# power.net
KiCad netlist of a schematic drawn in Altium Designer
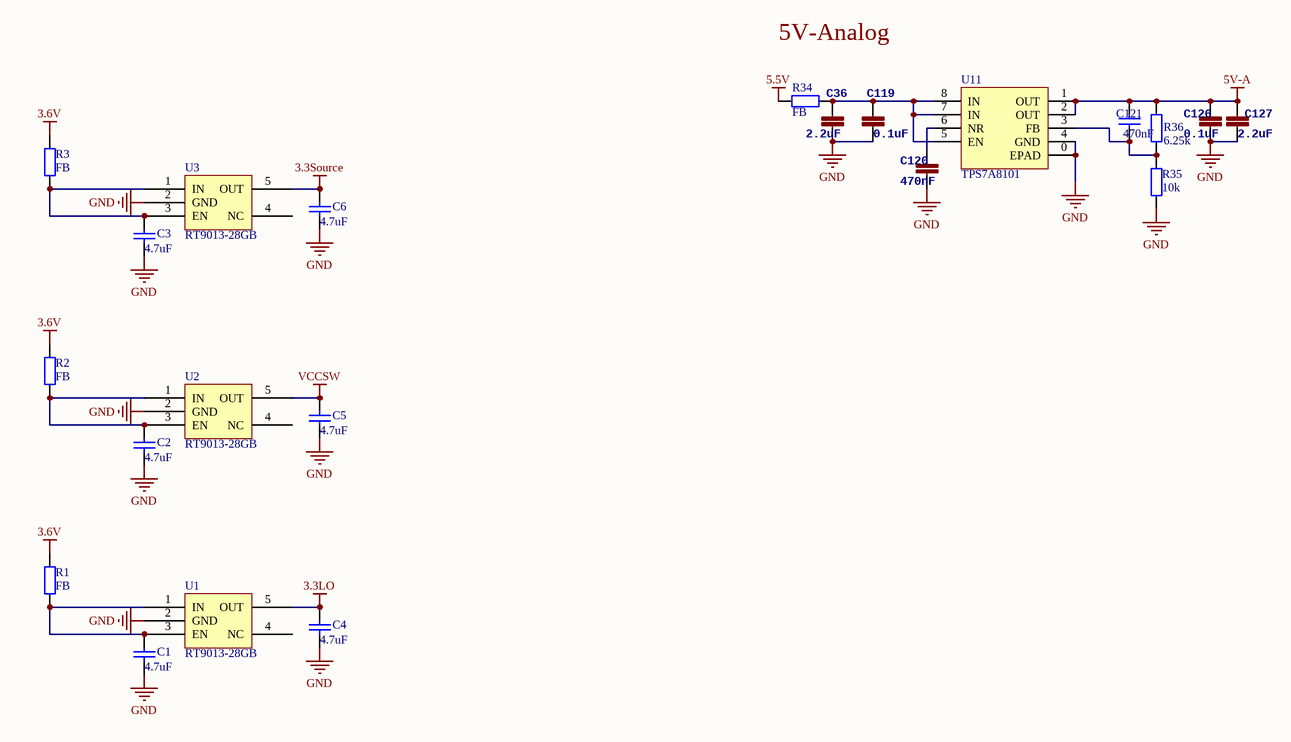
[diagram p0: power.SchDoc]

(export (version "E")
  (design (tool "Eeschema 10.0.6"))
  (components
    (comp (ref "C1")
      (value "4.7uF")
      (footprint "0603L")
      (description "Capacitor")
      (fields (field (name "PUBLISHER") "Altium Limited"))
      (libsource (lib "RTC6705") (part "Cap"))
    )
    (comp (ref "C2")
      (value "4.7uF")
      (footprint "0603L")
      (description "Capacitor")
      (fields (field (name "PUBLISHER") "Altium Limited"))
      (libsource (lib "RTC6705") (part "Cap"))
    )
    (comp (ref "C3")
      (value "4.7uF")
      (footprint "0603L")
      (description "Capacitor")
      (fields (field (name "PUBLISHER") "Altium Limited"))
      (libsource (lib "RTC6705") (part "Cap"))
    )
    (comp (ref "C4")
      (value "4.7uF")
      (footprint "0603L")
      (description "Capacitor")
      (fields (field (name "PUBLISHER") "Altium Limited"))
      (libsource (lib "RTC6705") (part "Cap"))
    )
    (comp (ref "C5")
      (value "4.7uF")
      (footprint "0603L")
      (description "Capacitor")
      (fields (field (name "PUBLISHER") "Altium Limited"))
      (libsource (lib "RTC6705") (part "Cap"))
    )
    (comp (ref "C6")
      (value "4.7uF")
      (footprint "0603L")
      (description "Capacitor")
      (fields (field (name "PUBLISHER") "Altium Limited"))
      (libsource (lib "RTC6705") (part "Cap"))
    )
    (comp (ref "C36")
      (value "2.2uF")
      (footprint "0603L")
      (description "<b>Capacitor</b>\nStandard 0603 ceramic capacitor, and 0.1\" leaded capacitor.")
      (fields (field (name "PARTNO") "CC0402ZRY5V7BB104"))
      (libsource (lib "pixhawk2") (part "CAP0402-CAP"))
    )
    (comp (ref "C119")
      (value "0.1uF")
      (footprint "0402")
      (description "<b>Capacitor</b>\nStandard 0603 ceramic capacitor, and 0.1\" leaded capacitor.")
      (fields (field (name "PARTNO") "CC0402ZRY5V7BB104"))
      (libsource (lib "*") (part "CAP0402-CAP"))
    )
    (comp (ref "C120")
      (value "470nF")
      (footprint "0402")
      (description "<b>Capacitor</b>\nStandard 0603 ceramic capacitor, and 0.1\" leaded capacitor.")
      (fields (field (name "PARTNO") "CC0402ZRY5V7BB104"))
      (libsource (lib "*") (part "CAP0402-CAP"))
    )
    (comp (ref "C121")
      (value "470nF")
      (footprint "0402")
      (description "Capacitor")
      (fields (field (name "PUBLISHER") "Altium Limited"))
      (libsource (lib "RTC6705") (part "Cap"))
    )
    (comp (ref "C126")
      (value "0.1uF")
      (footprint "0603L")
      (description "<b>Capacitor</b>\nStandard 0603 ceramic capacitor, and 0.1\" leaded capacitor.")
      (fields (field (name "PARTNO") "CC0402ZRY5V7BB104"))
      (libsource (lib "*") (part "CAP0402-CAP"))
    )
    (comp (ref "C127")
      (value "2.2uF")
      (footprint "0603L")
      (description "<b>Capacitor</b>\nStandard 0603 ceramic capacitor, and 0.1\" leaded capacitor.")
      (fields (field (name "PARTNO") "CC0402ZRY5V7BB104"))
      (libsource (lib "pixhawk2") (part "CAP0402-CAP"))
    )
    (comp (ref "R1")
      (value "FB")
      (footprint "0603L")
      (description "Resistor")
      (fields (field (name "PUBLISHER") "Altium Limited"))
      (libsource (lib "Miscellaneous Devices") (part "Res2"))
    )
    (comp (ref "R2")
      (value "FB")
      (footprint "0603L")
      (description "Resistor")
      (fields (field (name "PUBLISHER") "Altium Limited"))
      (libsource (lib "Miscellaneous Devices") (part "Res2"))
    )
    (comp (ref "R3")
      (value "FB")
      (footprint "0603L")
      (description "Resistor")
      (fields (field (name "PUBLISHER") "Altium Limited"))
      (libsource (lib "Miscellaneous Devices") (part "Res2"))
    )
    (comp (ref "R34")
      (value "FB")
      (footprint "0603L")
      (description "Resistor")
      (fields (field (name "PUBLISHER") "Altium Limited"))
      (libsource (lib "") (part "Res2_1"))
    )
    (comp (ref "R35")
      (value "10k")
      (footprint "0402")
      (description "Resistor")
      (fields (field (name "PUBLISHER") "Altium Limited"))
      (libsource (lib "") (part "Res2_2"))
    )
    (comp (ref "R36")
      (value "6.25k")
      (footprint "0402")
      (description "Resistor")
      (fields (field (name "PUBLISHER") "Altium Limited"))
      (libsource (lib "") (part "Res2_2"))
    )
    (comp (ref "U1") (value "RT9013-28GB") (footprint "SOT23-5") (libsource (lib "RTC6705") (part "LP5907")))
    (comp (ref "U2") (value "RT9013-28GB") (footprint "SOT23-5") (libsource (lib "RTC6705") (part "LP5907")))
    (comp (ref "U3") (value "RT9013-28GB") (footprint "SOT23-5") (libsource (lib "RTC6705") (part "LP5907")))
    (comp (ref "U11")
      (value "TPS7A8101")
      (footprint "TPS7A8101")
      (libsource (lib "F4SDR") (part "TPS7A8101"))
    )
  )
  (nets
    (net (code "1") (name "3.3LO") (class "Default")
      (node (ref "C4") (pin "2") (pinfunction "2_2") (pintype "passive"))
      (node (ref "U1") (pin "5") (pinfunction "OUT_5") (pintype "passive"))
    )
    (net (code "2") (name "3.3Source") (class "Default")
      (node (ref "C6") (pin "2") (pinfunction "2_2") (pintype "passive"))
      (node (ref "U3") (pin "5") (pinfunction "OUT_5") (pintype "passive"))
    )
    (net (code "3") (name "3.6V") (class "Default")
      (node (ref "R1") (pin "2") (pinfunction "2_2") (pintype "passive"))
      (node (ref "R2") (pin "2") (pinfunction "2_2") (pintype "passive"))
      (node (ref "R3") (pin "2") (pinfunction "2_2") (pintype "passive"))
    )
    (net (code "4") (name "5.5V") (class "Default")
      (node (ref "R34") (pin "2") (pinfunction "2_2") (pintype "passive"))
    )
    (net (code "5") (name "5V-A") (class "Default")
      (node (ref "C121") (pin "1") (pinfunction "1_1") (pintype "passive"))
      (node (ref "C126") (pin "2") (pinfunction "2_2") (pintype "passive"))
      (node (ref "C127") (pin "2") (pinfunction "2_2") (pintype "passive"))
      (node (ref "R36") (pin "1") (pinfunction "1_1") (pintype "passive"))
      (node (ref "U11") (pin "1") (pinfunction "OUT_1") (pintype "passive"))
      (node (ref "U11") (pin "2") (pinfunction "OUT_2") (pintype "passive"))
    )
    (net (code "6") (name "GND") (class "Default")
      (node (ref "C1") (pin "1") (pinfunction "1_1") (pintype "passive"))
      (node (ref "C119") (pin "1") (pinfunction "1_1") (pintype "passive"))
      (node (ref "C120") (pin "1") (pinfunction "1_1") (pintype "passive"))
      (node (ref "C126") (pin "1") (pinfunction "1_1") (pintype "passive"))
      (node (ref "C127") (pin "1") (pinfunction "1_1") (pintype "passive"))
      (node (ref "C2") (pin "1") (pinfunction "1_1") (pintype "passive"))
      (node (ref "C3") (pin "1") (pinfunction "1_1") (pintype "passive"))
      (node (ref "C36") (pin "1") (pinfunction "1_1") (pintype "passive"))
      (node (ref "C4") (pin "1") (pinfunction "1_1") (pintype "passive"))
      (node (ref "C5") (pin "1") (pinfunction "1_1") (pintype "passive"))
      (node (ref "C6") (pin "1") (pinfunction "1_1") (pintype "passive"))
      (node (ref "R35") (pin "2") (pinfunction "2_2") (pintype "passive"))
      (node (ref "U1") (pin "2") (pinfunction "GND_2") (pintype "passive"))
      (node (ref "U11") (pin "0") (pinfunction "EPAD_0") (pintype "passive"))
      (node (ref "U11") (pin "4") (pinfunction "GND_4") (pintype "passive"))
      (node (ref "U2") (pin "2") (pinfunction "GND_2") (pintype "passive"))
      (node (ref "U3") (pin "2") (pinfunction "GND_2") (pintype "passive"))
    )
    (net (code "7") (name "Net-(U1-EN)") (class "Default")
      (node (ref "C1") (pin "2") (pinfunction "2_2") (pintype "passive"))
      (node (ref "R1") (pin "1") (pinfunction "1_1") (pintype "passive"))
      (node (ref "U1") (pin "1") (pinfunction "IN_1") (pintype "passive"))
      (node (ref "U1") (pin "3") (pinfunction "EN_3") (pintype "passive"))
    )
    (net (code "8") (name "Net-(U2-EN)") (class "Default")
      (node (ref "C2") (pin "2") (pinfunction "2_2") (pintype "passive"))
      (node (ref "R2") (pin "1") (pinfunction "1_1") (pintype "passive"))
      (node (ref "U2") (pin "1") (pinfunction "IN_1") (pintype "passive"))
      (node (ref "U2") (pin "3") (pinfunction "EN_3") (pintype "passive"))
    )
    (net (code "9") (name "Net-(U3-EN)") (class "Default")
      (node (ref "C3") (pin "2") (pinfunction "2_2") (pintype "passive"))
      (node (ref "R3") (pin "1") (pinfunction "1_1") (pintype "passive"))
      (node (ref "U3") (pin "1") (pinfunction "IN_1") (pintype "passive"))
      (node (ref "U3") (pin "3") (pinfunction "EN_3") (pintype "passive"))
    )
    (net (code "10") (name "Net-(U11-EN)") (class "Default")
      (node (ref "C119") (pin "2") (pinfunction "2_2") (pintype "passive"))
      (node (ref "C36") (pin "2") (pinfunction "2_2") (pintype "passive"))
      (node (ref "R34") (pin "1") (pinfunction "1_1") (pintype "passive"))
      (node (ref "U11") (pin "5") (pinfunction "EN_5") (pintype "passive"))
      (node (ref "U11") (pin "7") (pinfunction "IN_7") (pintype "passive"))
      (node (ref "U11") (pin "8") (pinfunction "IN_8") (pintype "passive"))
    )
    (net (code "11") (name "Net-(U11-FB)") (class "Default")
      (node (ref "C121") (pin "2") (pinfunction "2_2") (pintype "passive"))
      (node (ref "R35") (pin "1") (pinfunction "1_1") (pintype "passive"))
      (node (ref "R36") (pin "2") (pinfunction "2_2") (pintype "passive"))
      (node (ref "U11") (pin "3") (pinfunction "FB_3") (pintype "passive"))
    )
    (net (code "12") (name "Net-(U11-NR)") (class "Default")
      (node (ref "C120") (pin "2") (pinfunction "2_2") (pintype "passive"))
      (node (ref "U11") (pin "6") (pinfunction "NR_6") (pintype "passive"))
    )
    (net (code "13") (name "VCCSW") (class "Default")
      (node (ref "C5") (pin "2") (pinfunction "2_2") (pintype "passive"))
      (node (ref "U2") (pin "5") (pinfunction "OUT_5") (pintype "passive"))
    )
    (net (code "14") (name "unconnected-(U1-NC-Pad4)") (class "Default")
      (node (ref "U1") (pin "4") (pinfunction "NC_4") (pintype "passive"))
    )
    (net (code "15") (name "unconnected-(U2-NC-Pad4)") (class "Default")
      (node (ref "U2") (pin "4") (pinfunction "NC_4") (pintype "passive"))
    )
    (net (code "16") (name "unconnected-(U3-NC-Pad4)") (class "Default")
      (node (ref "U3") (pin "4") (pinfunction "NC_4") (pintype "passive"))
    )
  )
)
